# schematic.net
KiCad netlist of a schematic drawn in EAGLE
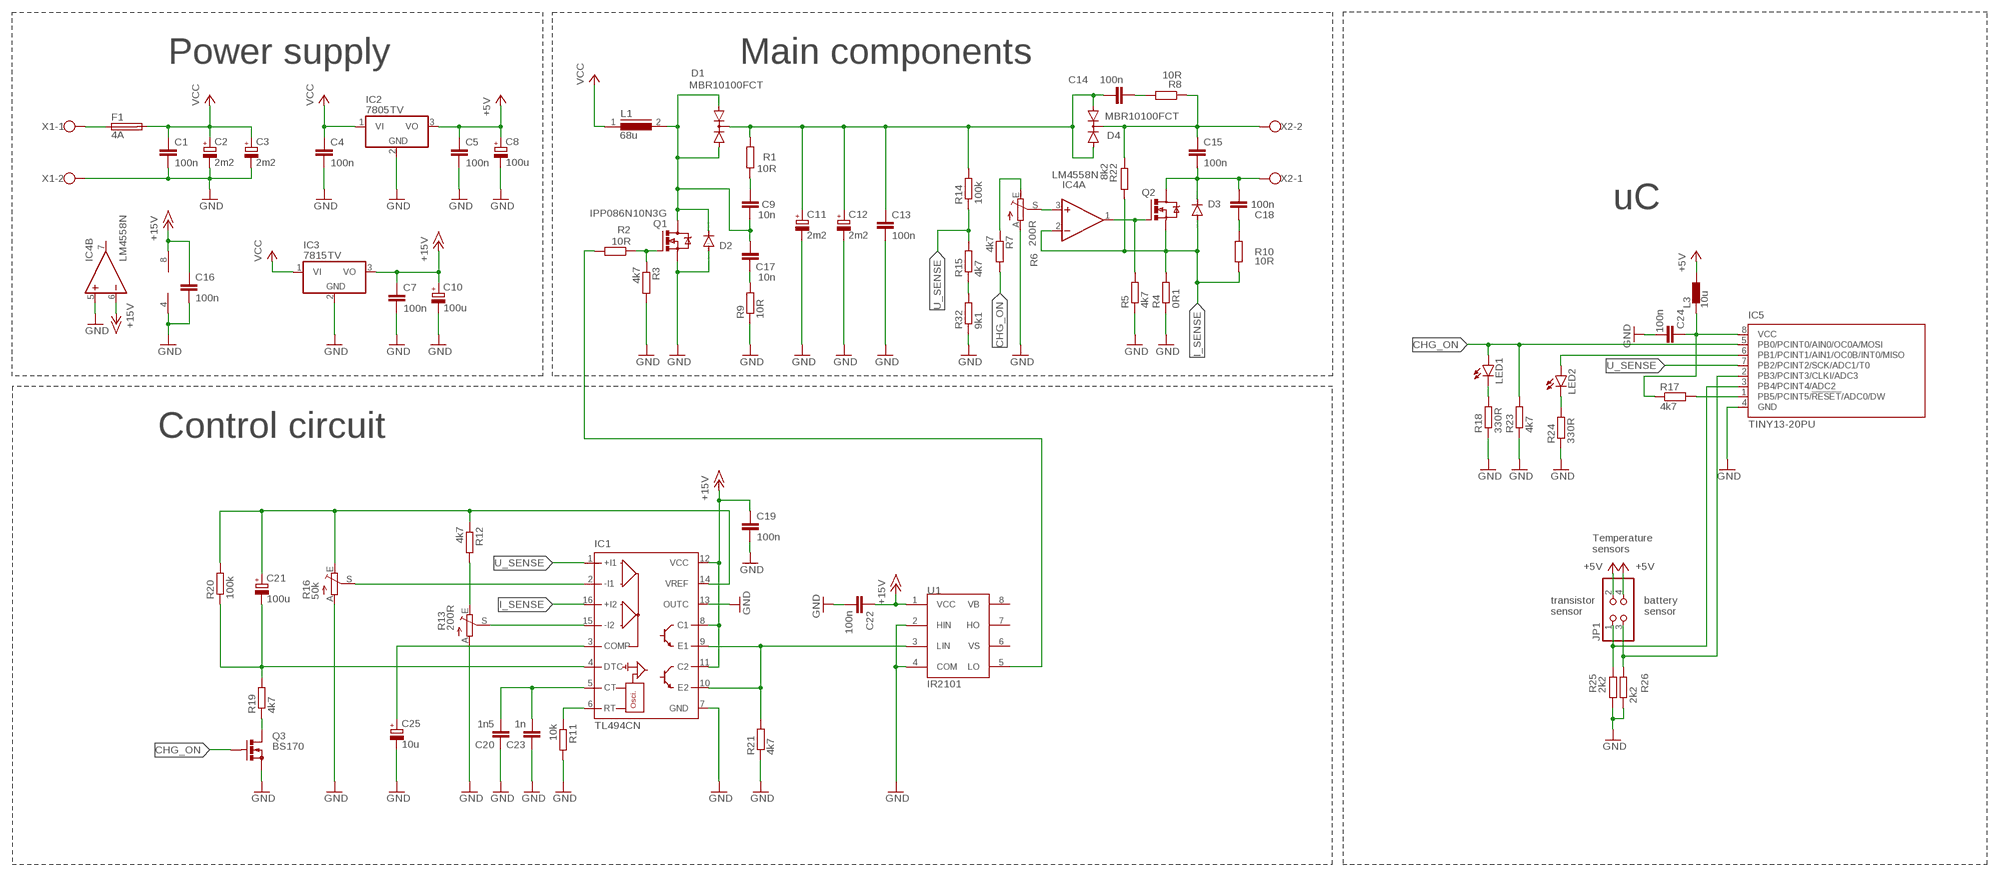
[diagram p0: schematic, sheet 1]

(export (version "E")
  (design (tool "Eeschema 10.0.6"))
  (components
    (comp (ref "C1")
      (value "100n")
      (footprint "eagle-import:C2.5-2")
      (libsource (lib "eagle-import") (part "C2.5/2"))
    )
    (comp (ref "C2")
      (value "2m2")
      (footprint "eagle-import:E7,5-16")
      (libsource (lib "eagle-import") (part "CPOL-EUE7.5-16"))
    )
    (comp (ref "C3")
      (value "2m2")
      (footprint "eagle-import:E7,5-16")
      (libsource (lib "eagle-import") (part "CPOL-EUE7.5-16"))
    )
    (comp (ref "C4")
      (value "100n")
      (footprint "eagle-import:C2.5-2")
      (libsource (lib "eagle-import") (part "C2.5/2"))
    )
    (comp (ref "C5")
      (value "100n")
      (footprint "eagle-import:C2.5-2")
      (libsource (lib "eagle-import") (part "C2.5/2"))
    )
    (comp (ref "C7")
      (value "100n")
      (footprint "eagle-import:C2.5-2")
      (libsource (lib "eagle-import") (part "C2.5/2"))
    )
    (comp (ref "C8")
      (value "100u")
      (footprint "eagle-import:E3,5-8")
      (libsource (lib "eagle-import") (part "CPOL-EUE3.5-8"))
    )
    (comp (ref "C9")
      (value "10n")
      (footprint "eagle-import:C2.5-2")
      (libsource (lib "eagle-import") (part "C2.5/2"))
    )
    (comp (ref "C10")
      (value "100u")
      (footprint "eagle-import:E3,5-8")
      (libsource (lib "eagle-import") (part "CPOL-EUE3.5-8"))
    )
    (comp (ref "C11")
      (value "2m2")
      (footprint "eagle-import:E7,5-18")
      (libsource (lib "eagle-import") (part "CPOL-EUE7.5-18"))
    )
    (comp (ref "C12")
      (value "2m2")
      (footprint "eagle-import:E7,5-18")
      (libsource (lib "eagle-import") (part "CPOL-EUE7.5-18"))
    )
    (comp (ref "C13")
      (value "100n")
      (footprint "eagle-import:C2.5-2")
      (libsource (lib "eagle-import") (part "C2.5/2"))
    )
    (comp (ref "C14")
      (value "100n")
      (footprint "eagle-import:C2.5-2")
      (libsource (lib "eagle-import") (part "C2.5/2"))
    )
    (comp (ref "C15")
      (value "100n")
      (footprint "eagle-import:C2.5-2")
      (libsource (lib "eagle-import") (part "C2.5/2"))
    )
    (comp (ref "C16")
      (value "100n")
      (footprint "eagle-import:C2.5-2")
      (libsource (lib "eagle-import") (part "C2.5/2"))
    )
    (comp (ref "C17")
      (value "10n")
      (footprint "eagle-import:C2.5-2")
      (libsource (lib "eagle-import") (part "C2.5/2"))
    )
    (comp (ref "C18")
      (value "100n")
      (footprint "eagle-import:C2.5-2")
      (libsource (lib "eagle-import") (part "C2.5/2"))
    )
    (comp (ref "C19")
      (value "100n")
      (footprint "eagle-import:C2.5-2")
      (libsource (lib "eagle-import") (part "C2.5/2"))
    )
    (comp (ref "C20")
      (value "1n5")
      (footprint "eagle-import:C2.5-2")
      (libsource (lib "eagle-import") (part "C2.5/2"))
    )
    (comp (ref "C21")
      (value "100u")
      (footprint "eagle-import:E3,5-8")
      (libsource (lib "eagle-import") (part "CPOL-EUE3.5-8"))
    )
    (comp (ref "C22")
      (value "100n")
      (footprint "eagle-import:C2.5-2")
      (libsource (lib "eagle-import") (part "C2.5/2"))
    )
    (comp (ref "C23")
      (value "1n")
      (footprint "eagle-import:C2.5-2")
      (libsource (lib "eagle-import") (part "C2.5/2"))
    )
    (comp (ref "C24")
      (value "100n")
      (footprint "eagle-import:C2.5-2")
      (libsource (lib "eagle-import") (part "C2.5/2"))
    )
    (comp (ref "C25")
      (value "10u")
      (footprint "eagle-import:E2,5-5")
      (libsource (lib "eagle-import") (part "CPOL-EUE2.5-5"))
    )
    (comp (ref "D1")
      (value "MBR10100FCT")
      (footprint "eagle-import:TO220ABS")
      (libsource (lib "eagle-import") (part "BYV32"))
    )
    (comp (ref "D2")
      (value "1N4933")
      (footprint "eagle-import:DO41-10")
      (libsource (lib "eagle-import") (part "1N4933"))
    )
    (comp (ref "D3")
      (value "1N4933")
      (footprint "eagle-import:DO41-10")
      (libsource (lib "eagle-import") (part "1N4933"))
    )
    (comp (ref "D4")
      (value "MBR10100FCT")
      (footprint "eagle-import:TO220ABS")
      (libsource (lib "eagle-import") (part "BYV32"))
    )
    (comp (ref "F1")
      (value "4A")
      (footprint "eagle-import:SH22")
      (libsource (lib "eagle-import") (part "SH22"))
    )
    (comp (ref "IC1")
      (value "TL494CN")
      (footprint "eagle-import:DIL16")
      (libsource (lib "eagle-import") (part "TL494NC"))
    )
    (comp (ref "IC2")
      (value "7805TV")
      (footprint "eagle-import:TO220V")
      (libsource (lib "eagle-import") (part "78TV05"))
    )
    (comp (ref "IC3")
      (value "7815TV")
      (footprint "eagle-import:TO220V")
      (libsource (lib "eagle-import") (part "78TV15"))
    )
    (comp (ref "IC4")
      (value "LM4558N")
      (footprint "eagle-import:DIL08")
      (libsource (lib "eagle-import") (part "4558NLM"))
    )
    (comp (ref "IC5")
      (value "TINY13-20PU")
      (footprint "eagle-import:DIL08")
      (fields (field (name "MPN") "ATTINY13-20PU"))
      (libsource (lib "eagle-import") (part "TINY13PU-20"))
    )
    (comp (ref "JP1")
      (value "PINHD-2X2")
      (footprint "eagle-import:2X02")
      (libsource (lib "eagle-import") (part "PINHD-2X2"))
    )
    (comp (ref "L1")
      (value "68u")
      (footprint "eagle-import:SFT1240")
      (libsource (lib "eagle-import") (part "SFT1240"))
    )
    (comp (ref "L3")
      (value "10u")
      (footprint "eagle-import:BL01RN1A")
      (libsource (lib "eagle-import") (part "BL01RN1A"))
    )
    (comp (ref "LED1")
      (value "LED5MM")
      (footprint "eagle-import:LED5MM")
      (libsource (lib "eagle-import") (part "LED5MM"))
    )
    (comp (ref "LED2")
      (value "LED5MM")
      (footprint "eagle-import:LED5MM")
      (libsource (lib "eagle-import") (part "LED5MM"))
    )
    (comp (ref "Q1")
      (value "IPP086N10N3G")
      (footprint "eagle-import:TO220BV")
      (libsource (lib "eagle-import") (part "IRF520"))
    )
    (comp (ref "Q2")
      (value "IRF520")
      (footprint "eagle-import:TO220BV")
      (libsource (lib "eagle-import") (part "IRF520"))
    )
    (comp (ref "Q3")
      (value "BS170")
      (footprint "eagle-import:SOT54E")
      (libsource (lib "eagle-import") (part "BS170"))
    )
    (comp (ref "R1")
      (value "10R")
      (footprint "eagle-import:0204_7")
      (libsource (lib "eagle-import") (part "R-EU_0204/7"))
    )
    (comp (ref "R2")
      (value "10R")
      (footprint "eagle-import:0204_7")
      (libsource (lib "eagle-import") (part "R-EU_0204/7"))
    )
    (comp (ref "R3")
      (value "4k7")
      (footprint "eagle-import:0204_7")
      (libsource (lib "eagle-import") (part "R-EU_0204/7"))
    )
    (comp (ref "R4")
      (value "0R1")
      (footprint "eagle-import:0204_5")
      (libsource (lib "eagle-import") (part "R-EU_0204/5"))
    )
    (comp (ref "R5")
      (value "4k7")
      (footprint "eagle-import:0204_7")
      (libsource (lib "eagle-import") (part "R-EU_0204/7"))
    )
    (comp (ref "R6")
      (value "200R")
      (footprint "eagle-import:B64Y")
      (libsource (lib "eagle-import") (part "TRIM_EU-B64Y"))
    )
    (comp (ref "R7")
      (value "4k7")
      (footprint "eagle-import:0204_7")
      (libsource (lib "eagle-import") (part "R-EU_0204/7"))
    )
    (comp (ref "R8")
      (value "10R")
      (footprint "eagle-import:0204_7")
      (libsource (lib "eagle-import") (part "R-EU_0204/7"))
    )
    (comp (ref "R9")
      (value "10R")
      (footprint "eagle-import:0204_7")
      (libsource (lib "eagle-import") (part "R-EU_0204/7"))
    )
    (comp (ref "R10")
      (value "10R")
      (footprint "eagle-import:0204_7")
      (libsource (lib "eagle-import") (part "R-EU_0204/7"))
    )
    (comp (ref "R11")
      (value "10k")
      (footprint "eagle-import:0204_7")
      (libsource (lib "eagle-import") (part "R-EU_0204/7"))
    )
    (comp (ref "R12")
      (value "4k7")
      (footprint "eagle-import:0204_7")
      (libsource (lib "eagle-import") (part "R-EU_0204/7"))
    )
    (comp (ref "R13")
      (value "200R")
      (footprint "eagle-import:B64Y")
      (libsource (lib "eagle-import") (part "TRIM_EU-B64Y"))
    )
    (comp (ref "R14")
      (value "100k")
      (footprint "eagle-import:0204_7")
      (libsource (lib "eagle-import") (part "R-EU_0204/7"))
    )
    (comp (ref "R15")
      (value "4k7")
      (footprint "eagle-import:0204_7")
      (libsource (lib "eagle-import") (part "R-EU_0204/7"))
    )
    (comp (ref "R16")
      (value "50k")
      (footprint "eagle-import:B64W")
      (libsource (lib "eagle-import") (part "TRIM_EU-B64W"))
    )
    (comp (ref "R17")
      (value "4k7")
      (footprint "eagle-import:0204_7")
      (libsource (lib "eagle-import") (part "R-EU_0204/7"))
    )
    (comp (ref "R18")
      (value "330R")
      (footprint "eagle-import:0204_7")
      (libsource (lib "eagle-import") (part "R-EU_0204/7"))
    )
    (comp (ref "R19")
      (value "4k7")
      (footprint "eagle-import:0204_7")
      (libsource (lib "eagle-import") (part "R-EU_0204/7"))
    )
    (comp (ref "R20")
      (value "100k")
      (footprint "eagle-import:0204_7")
      (libsource (lib "eagle-import") (part "R-EU_0204/7"))
    )
    (comp (ref "R21")
      (value "4k7")
      (footprint "eagle-import:0204_7")
      (libsource (lib "eagle-import") (part "R-EU_0204/7"))
    )
    (comp (ref "R22")
      (value "8k2")
      (footprint "eagle-import:0204_7")
      (libsource (lib "eagle-import") (part "R-EU_0204/7"))
    )
    (comp (ref "R23")
      (value "4k7")
      (footprint "eagle-import:0204_7")
      (libsource (lib "eagle-import") (part "R-EU_0204/7"))
    )
    (comp (ref "R24")
      (value "330R")
      (footprint "eagle-import:0204_7")
      (libsource (lib "eagle-import") (part "R-EU_0204/7"))
    )
    (comp (ref "R25")
      (value "2k2")
      (footprint "eagle-import:0204_7")
      (libsource (lib "eagle-import") (part "R-EU_0204/7"))
    )
    (comp (ref "R26")
      (value "2k2")
      (footprint "eagle-import:0204_7")
      (libsource (lib "eagle-import") (part "R-EU_0204/7"))
    )
    (comp (ref "R32")
      (value "9k1")
      (footprint "eagle-import:0204_7")
      (libsource (lib "eagle-import") (part "R-EU_0204/7"))
    )
    (comp (ref "U1")
      (value "IR2101")
      (footprint "eagle-import:DIL08")
      (libsource (lib "eagle-import") (part "IR2101"))
    )
    (comp (ref "X1")
      (value "W237-102")
      (footprint "eagle-import:W237-102")
      (fields (field (name "MPN") "237-102"))
      (libsource (lib "eagle-import") (part "W237-102"))
    )
    (comp (ref "X2")
      (value "W237-102")
      (footprint "eagle-import:W237-102")
      (fields (field (name "MPN") "237-102"))
      (libsource (lib "eagle-import") (part "W237-102"))
    )
  )
  (nets
    (net (code "1") (name "+5V") (class "Default")
      (node (ref "C5") (pin "1") (pinfunction "1_1") (pintype "passive"))
      (node (ref "C8") (pin "+") (pinfunction "+_+") (pintype "passive"))
      (node (ref "IC2") (pin "3") (pinfunction "VO_3") (pintype "passive"))
      (node (ref "JP1") (pin "2") (pinfunction "2_2") (pintype "passive"))
      (node (ref "JP1") (pin "4") (pinfunction "4_4") (pintype "passive"))
      (node (ref "L3") (pin "2") (pinfunction "2_2") (pintype "passive"))
    )
    (net (code "2") (name "+15V") (class "Default")
      (node (ref "C10") (pin "+") (pinfunction "+_+") (pintype "passive"))
      (node (ref "C16") (pin "1") (pinfunction "1_1") (pintype "passive"))
      (node (ref "C19") (pin "1") (pinfunction "1_1") (pintype "passive"))
      (node (ref "C22") (pin "1") (pinfunction "1_1") (pintype "passive"))
      (node (ref "C7") (pin "1") (pinfunction "1_1") (pintype "passive"))
      (node (ref "IC1") (pin "11") (pinfunction "C2_11") (pintype "passive"))
      (node (ref "IC1") (pin "12") (pinfunction "VCC_12") (pintype "power_in"))
      (node (ref "IC1") (pin "8") (pinfunction "C1_8") (pintype "passive"))
      (node (ref "IC3") (pin "3") (pinfunction "VO_3") (pintype "passive"))
      (node (ref "IC4") (pin "6") (pinfunction "-IN_6") (pintype "input"))
      (node (ref "IC4") (pin "8") (pinfunction "V+_8") (pintype "power_in"))
      (node (ref "U1") (pin "1") (pinfunction "VCC_1") (pintype "power_in"))
    )
    (net (code "3") (name "/VB") (class "Default")
      (node (ref "U1") (pin "8") (pinfunction "VB_8") (pintype "power_in"))
    )
    (net (code "4") (name "CHG_ON") (class "Default")
      (node (ref "IC5") (pin "5") (pinfunction "PB0/PCINT0/AIN0/OC0A/MOSI_5") (pintype "bidirectional"))
      (node (ref "LED1") (pin "A") (pinfunction "A_A") (pintype "passive"))
      (node (ref "Q3") (pin "G") (pinfunction "G_G") (pintype "passive"))
      (node (ref "R23") (pin "2") (pinfunction "2_2") (pintype "passive"))
      (node (ref "R7") (pin "2") (pinfunction "2_2") (pintype "passive"))
    )
    (net (code "5") (name "GND") (class "Default")
      (node (ref "C1") (pin "2") (pinfunction "2_2") (pintype "passive"))
      (node (ref "C10") (pin "-") (pinfunction "-_-") (pintype "passive"))
      (node (ref "C11") (pin "-") (pinfunction "-_-") (pintype "passive"))
      (node (ref "C12") (pin "-") (pinfunction "-_-") (pintype "passive"))
      (node (ref "C13") (pin "2") (pinfunction "2_2") (pintype "passive"))
      (node (ref "C16") (pin "2") (pinfunction "2_2") (pintype "passive"))
      (node (ref "C19") (pin "2") (pinfunction "2_2") (pintype "passive"))
      (node (ref "C2") (pin "-") (pinfunction "-_-") (pintype "passive"))
      (node (ref "C20") (pin "1") (pinfunction "1_1") (pintype "passive"))
      (node (ref "C22") (pin "2") (pinfunction "2_2") (pintype "passive"))
      (node (ref "C23") (pin "1") (pinfunction "1_1") (pintype "passive"))
      (node (ref "C24") (pin "2") (pinfunction "2_2") (pintype "passive"))
      (node (ref "C25") (pin "-") (pinfunction "-_-") (pintype "passive"))
      (node (ref "C3") (pin "-") (pinfunction "-_-") (pintype "passive"))
      (node (ref "C4") (pin "2") (pinfunction "2_2") (pintype "passive"))
      (node (ref "C5") (pin "2") (pinfunction "2_2") (pintype "passive"))
      (node (ref "C7") (pin "2") (pinfunction "2_2") (pintype "passive"))
      (node (ref "C8") (pin "-") (pinfunction "-_-") (pintype "passive"))
      (node (ref "D2") (pin "A") (pinfunction "A_A") (pintype "passive"))
      (node (ref "IC1") (pin "13") (pinfunction "OUTC_13") (pintype "output"))
      (node (ref "IC1") (pin "7") (pinfunction "GND_7") (pintype "power_in"))
      (node (ref "IC2") (pin "2") (pinfunction "GND_2") (pintype "passive"))
      (node (ref "IC3") (pin "2") (pinfunction "GND_2") (pintype "passive"))
      (node (ref "IC4") (pin "4") (pinfunction "V-_4") (pintype "power_in"))
      (node (ref "IC4") (pin "5") (pinfunction "+IN_5") (pintype "input"))
      (node (ref "IC5") (pin "4") (pinfunction "GND_4") (pintype "power_in"))
      (node (ref "Q1") (pin "S") (pinfunction "S_S") (pintype "passive"))
      (node (ref "Q3") (pin "S") (pinfunction "S_S") (pintype "passive"))
      (node (ref "R11") (pin "2") (pinfunction "2_2") (pintype "passive"))
      (node (ref "R13") (pin "A") (pinfunction "A_A") (pintype "passive"))
      (node (ref "R16") (pin "A") (pinfunction "A_A") (pintype "passive"))
      (node (ref "R18") (pin "1") (pinfunction "1_1") (pintype "passive"))
      (node (ref "R21") (pin "1") (pinfunction "1_1") (pintype "passive"))
      (node (ref "R23") (pin "1") (pinfunction "1_1") (pintype "passive"))
      (node (ref "R24") (pin "1") (pinfunction "1_1") (pintype "passive"))
      (node (ref "R25") (pin "1") (pinfunction "1_1") (pintype "passive"))
      (node (ref "R26") (pin "1") (pinfunction "1_1") (pintype "passive"))
      (node (ref "R3") (pin "2") (pinfunction "2_2") (pintype "passive"))
      (node (ref "R32") (pin "1") (pinfunction "1_1") (pintype "passive"))
      (node (ref "R4") (pin "1") (pinfunction "1_1") (pintype "passive"))
      (node (ref "R5") (pin "1") (pinfunction "1_1") (pintype "passive"))
      (node (ref "R6") (pin "A") (pinfunction "A_A") (pintype "passive"))
      (node (ref "R9") (pin "1") (pinfunction "1_1") (pintype "passive"))
      (node (ref "U1") (pin "2") (pinfunction "HIN_2") (pintype "input"))
      (node (ref "U1") (pin "4") (pinfunction "COM_4") (pintype "power_in"))
      (node (ref "X1") (pin "2") (pinfunction "KL_2") (pintype "passive"))
    )
    (net (code "6") (name "I_SENSE") (class "Default")
      (node (ref "D3") (pin "A") (pinfunction "A_A") (pintype "passive"))
      (node (ref "IC1") (pin "16") (pinfunction "+I2_16") (pintype "input"))
      (node (ref "IC4") (pin "2") (pinfunction "-IN_2") (pintype "input"))
      (node (ref "Q2") (pin "S") (pinfunction "S_S") (pintype "passive"))
      (node (ref "R10") (pin "2") (pinfunction "2_2") (pintype "passive"))
      (node (ref "R22") (pin "2") (pinfunction "2_2") (pintype "passive"))
      (node (ref "R4") (pin "2") (pinfunction "2_2") (pintype "passive"))
    )
    (net (code "7") (name "Net-(C9-Pad1)") (class "Default")
      (node (ref "C9") (pin "1") (pinfunction "1_1") (pintype "passive"))
      (node (ref "R1") (pin "1") (pinfunction "1_1") (pintype "passive"))
    )
    (net (code "8") (name "Net-(C11-Pad+)") (class "Default")
      (node (ref "C11") (pin "+") (pinfunction "+_+") (pintype "passive"))
      (node (ref "C12") (pin "+") (pinfunction "+_+") (pintype "passive"))
      (node (ref "C13") (pin "1") (pinfunction "1_1") (pintype "passive"))
      (node (ref "C14") (pin "2") (pinfunction "2_2") (pintype "passive"))
      (node (ref "D1") (pin "C") (pinfunction "C_C") (pintype "passive"))
      (node (ref "D4") (pin "A1") (pinfunction "A1_A1") (pintype "passive"))
      (node (ref "D4") (pin "A2") (pinfunction "A2_A2") (pintype "passive"))
      (node (ref "R1") (pin "2") (pinfunction "2_2") (pintype "passive"))
      (node (ref "R14") (pin "2") (pinfunction "2_2") (pintype "passive"))
    )
    (net (code "9") (name "Net-(C14-Pad1)") (class "Default")
      (node (ref "C14") (pin "1") (pinfunction "1_1") (pintype "passive"))
      (node (ref "R8") (pin "2") (pinfunction "2_2") (pintype "passive"))
    )
    (net (code "10") (name "Net-(C17-Pad1)") (class "Default")
      (node (ref "C17") (pin "1") (pinfunction "1_1") (pintype "passive"))
      (node (ref "C9") (pin "2") (pinfunction "2_2") (pintype "passive"))
      (node (ref "D1") (pin "A1") (pinfunction "A1_A1") (pintype "passive"))
      (node (ref "D1") (pin "A2") (pinfunction "A2_A2") (pintype "passive"))
      (node (ref "D2") (pin "C") (pinfunction "C_C") (pintype "passive"))
      (node (ref "L1") (pin "2") (pinfunction "2_2") (pintype "passive"))
      (node (ref "Q1") (pin "D") (pinfunction "D_D") (pintype "passive"))
    )
    (net (code "11") (name "Net-(C17-Pad2)") (class "Default")
      (node (ref "C17") (pin "2") (pinfunction "2_2") (pintype "passive"))
      (node (ref "R9") (pin "2") (pinfunction "2_2") (pintype "passive"))
    )
    (net (code "12") (name "Net-(C18-Pad2)") (class "Default")
      (node (ref "C18") (pin "2") (pinfunction "2_2") (pintype "passive"))
      (node (ref "R10") (pin "1") (pinfunction "1_1") (pintype "passive"))
    )
    (net (code "13") (name "Net-(IC1--I1)") (class "Default")
      (node (ref "IC1") (pin "2") (pinfunction "-I1_2") (pintype "input"))
      (node (ref "R16") (pin "S") (pinfunction "S_S") (pintype "passive"))
    )
    (net (code "14") (name "Net-(IC1--I2)") (class "Default")
      (node (ref "IC1") (pin "15") (pinfunction "-I2_15") (pintype "input"))
      (node (ref "R13") (pin "S") (pinfunction "S_S") (pintype "passive"))
    )
    (net (code "15") (name "Net-(IC1-COMP)") (class "Default")
      (node (ref "C25") (pin "+") (pinfunction "+_+") (pintype "passive"))
      (node (ref "IC1") (pin "3") (pinfunction "COMP_3") (pintype "passive"))
    )
    (net (code "16") (name "Net-(IC1-CT)") (class "Default")
      (node (ref "C20") (pin "2") (pinfunction "2_2") (pintype "passive"))
      (node (ref "C23") (pin "2") (pinfunction "2_2") (pintype "passive"))
      (node (ref "IC1") (pin "5") (pinfunction "CT_5") (pintype "input"))
    )
    (net (code "17") (name "Net-(IC1-DTC)") (class "Default")
      (node (ref "C21") (pin "-") (pinfunction "-_-") (pintype "passive"))
      (node (ref "IC1") (pin "4") (pinfunction "DTC_4") (pintype "input"))
      (node (ref "R19") (pin "2") (pinfunction "2_2") (pintype "passive"))
      (node (ref "R20") (pin "1") (pinfunction "1_1") (pintype "passive"))
    )
    (net (code "18") (name "Net-(IC1-E1)") (class "Default")
      (node (ref "IC1") (pin "10") (pinfunction "E2_10") (pintype "passive"))
      (node (ref "IC1") (pin "9") (pinfunction "E1_9") (pintype "passive"))
      (node (ref "R21") (pin "2") (pinfunction "2_2") (pintype "passive"))
      (node (ref "U1") (pin "3") (pinfunction "LIN_3") (pintype "input"))
    )
    (net (code "19") (name "Net-(IC1-RT)") (class "Default")
      (node (ref "IC1") (pin "6") (pinfunction "RT_6") (pintype "input"))
      (node (ref "R11") (pin "1") (pinfunction "1_1") (pintype "passive"))
    )
    (net (code "20") (name "Net-(IC1-VREF)") (class "Default")
      (node (ref "C21") (pin "+") (pinfunction "+_+") (pintype "passive"))
      (node (ref "IC1") (pin "14") (pinfunction "VREF_14") (pintype "input"))
      (node (ref "R12") (pin "1") (pinfunction "1_1") (pintype "passive"))
      (node (ref "R16") (pin "E") (pinfunction "E_E") (pintype "passive"))
      (node (ref "R20") (pin "2") (pinfunction "2_2") (pintype "passive"))
    )
    (net (code "21") (name "Net-(IC4A-+IN)") (class "Default")
      (node (ref "IC4") (pin "3") (pinfunction "+IN_3") (pintype "input"))
      (node (ref "R6") (pin "S") (pinfunction "S_S") (pintype "passive"))
    )
    (net (code "22") (name "Net-(IC4A-OUT)") (class "Default")
      (node (ref "IC4") (pin "1") (pinfunction "OUT_1") (pintype "output"))
      (node (ref "Q2") (pin "G") (pinfunction "G_G") (pintype "passive"))
      (node (ref "R5") (pin "2") (pinfunction "2_2") (pintype "passive"))
    )
    (net (code "23") (name "Net-(IC5-PB1{slash}PCINT1{slash}AIN1{slash}OC0B{slash}INT0{slash}MISO)") (class "Default")
      (node (ref "IC5") (pin "6") (pinfunction "PB1/PCINT1/AIN1/OC0B/INT0/MISO_6") (pintype "bidirectional"))
      (node (ref "LED2") (pin "A") (pinfunction "A_A") (pintype "passive"))
    )
    (net (code "24") (name "Net-(IC5-PB3{slash}PCINT3{slash}CLKI{slash}ADC3)") (class "Default")
      (node (ref "IC5") (pin "2") (pinfunction "PB3/PCINT3/CLKI/ADC3_2") (pintype "bidirectional"))
      (node (ref "JP1") (pin "3") (pinfunction "3_3") (pintype "passive"))
      (node (ref "R26") (pin "2") (pinfunction "2_2") (pintype "passive"))
    )
    (net (code "25") (name "Net-(IC5-PB4{slash}PCINT4{slash}ADC2)") (class "Default")
      (node (ref "IC5") (pin "3") (pinfunction "PB4/PCINT4/ADC2_3") (pintype "bidirectional"))
      (node (ref "JP1") (pin "1") (pinfunction "1_1") (pintype "passive"))
      (node (ref "R25") (pin "2") (pinfunction "2_2") (pintype "passive"))
    )
    (net (code "26") (name "Net-(IC5-PB5{slash}PCINT5{slash}~{RESET}{slash}ADC0{slash}DW)") (class "Default")
      (node (ref "IC5") (pin "1") (pinfunction "PB5/PCINT5/~{RESET}/ADC0/DW_1") (pintype "bidirectional"))
      (node (ref "R17") (pin "2") (pinfunction "2_2") (pintype "passive"))
    )
    (net (code "27") (name "Net-(IC5-VCC)") (class "Default")
      (node (ref "C24") (pin "1") (pinfunction "1_1") (pintype "passive"))
      (node (ref "IC5") (pin "8") (pinfunction "VCC_8") (pintype "power_in"))
      (node (ref "L3") (pin "1") (pinfunction "1_1") (pintype "passive"))
      (node (ref "R17") (pin "1") (pinfunction "1_1") (pintype "passive"))
    )
    (net (code "28") (name "Net-(LED1-C)") (class "Default")
      (node (ref "LED1") (pin "K") (pinfunction "C_K") (pintype "passive"))
      (node (ref "R18") (pin "2") (pinfunction "2_2") (pintype "passive"))
    )
    (net (code "29") (name "Net-(LED2-C)") (class "Default")
      (node (ref "LED2") (pin "K") (pinfunction "C_K") (pintype "passive"))
      (node (ref "R24") (pin "2") (pinfunction "2_2") (pintype "passive"))
    )
    (net (code "30") (name "Net-(Q1-PadG)") (class "Default")
      (node (ref "Q1") (pin "G") (pinfunction "G_G") (pintype "passive"))
      (node (ref "R2") (pin "1") (pinfunction "1_1") (pintype "passive"))
      (node (ref "R3") (pin "1") (pinfunction "1_1") (pintype "passive"))
    )
    (net (code "31") (name "Net-(Q3-PadD)") (class "Default")
      (node (ref "Q3") (pin "D") (pinfunction "D_D") (pintype "passive"))
      (node (ref "R19") (pin "1") (pinfunction "1_1") (pintype "passive"))
    )
    (net (code "32") (name "Net-(R6-PadE)") (class "Default")
      (node (ref "R6") (pin "E") (pinfunction "E_E") (pintype "passive"))
      (node (ref "R7") (pin "1") (pinfunction "1_1") (pintype "passive"))
    )
    (net (code "33") (name "Net-(R12-Pad2)") (class "Default")
      (node (ref "R12") (pin "2") (pinfunction "2_2") (pintype "passive"))
      (node (ref "R13") (pin "E") (pinfunction "E_E") (pintype "passive"))
    )
    (net (code "34") (name "Net-(R15-Pad1)") (class "Default")
      (node (ref "R15") (pin "1") (pinfunction "1_1") (pintype "passive"))
      (node (ref "R32") (pin "2") (pinfunction "2_2") (pintype "passive"))
    )
    (net (code "35") (name "Net-(U1-LO)") (class "Default")
      (node (ref "R2") (pin "2") (pinfunction "2_2") (pintype "passive"))
      (node (ref "U1") (pin "5") (pinfunction "LO_5") (pintype "output"))
    )
    (net (code "36") (name "Net-(X1A-KL)") (class "Default")
      (node (ref "F1") (pin "1") (pinfunction "1_1") (pintype "passive"))
      (node (ref "X1") (pin "1") (pinfunction "KL_1") (pintype "passive"))
    )
    (net (code "37") (name "Net-(X2A-KL)") (class "Default")
      (node (ref "C15") (pin "2") (pinfunction "2_2") (pintype "passive"))
      (node (ref "C18") (pin "1") (pinfunction "1_1") (pintype "passive"))
      (node (ref "D3") (pin "C") (pinfunction "C_C") (pintype "passive"))
      (node (ref "Q2") (pin "D") (pinfunction "D_D") (pintype "passive"))
      (node (ref "X2") (pin "1") (pinfunction "KL_1") (pintype "passive"))
    )
    (net (code "38") (name "Net-(X2B-KL)") (class "Default")
      (node (ref "C15") (pin "1") (pinfunction "1_1") (pintype "passive"))
      (node (ref "D4") (pin "C") (pinfunction "C_C") (pintype "passive"))
      (node (ref "R22") (pin "1") (pinfunction "1_1") (pintype "passive"))
      (node (ref "R8") (pin "1") (pinfunction "1_1") (pintype "passive"))
      (node (ref "X2") (pin "2") (pinfunction "KL_2") (pintype "passive"))
    )
    (net (code "39") (name "U_SENSE") (class "Default")
      (node (ref "IC1") (pin "1") (pinfunction "+I1_1") (pintype "input"))
      (node (ref "IC5") (pin "7") (pinfunction "PB2/PCINT2/SCK/ADC1/T0_7") (pintype "bidirectional"))
      (node (ref "R14") (pin "1") (pinfunction "1_1") (pintype "passive"))
      (node (ref "R15") (pin "2") (pinfunction "2_2") (pintype "passive"))
    )
    (net (code "40") (name "VCC") (class "Default")
      (node (ref "C1") (pin "1") (pinfunction "1_1") (pintype "passive"))
      (node (ref "C2") (pin "+") (pinfunction "+_+") (pintype "passive"))
      (node (ref "C3") (pin "+") (pinfunction "+_+") (pintype "passive"))
      (node (ref "C4") (pin "1") (pinfunction "1_1") (pintype "passive"))
      (node (ref "F1") (pin "2") (pinfunction "2_2") (pintype "passive"))
      (node (ref "IC2") (pin "1") (pinfunction "VI_1") (pintype "input"))
      (node (ref "IC3") (pin "1") (pinfunction "VI_1") (pintype "input"))
      (node (ref "L1") (pin "1") (pinfunction "1_1") (pintype "passive"))
    )
    (net (code "41") (name "unconnected-(IC4B-OUT-Pad7)") (class "Default")
      (node (ref "IC4") (pin "7") (pinfunction "OUT_7") (pintype "output"))
    )
    (net (code "42") (name "unconnected-(U1-HO-Pad7)") (class "Default")
      (node (ref "U1") (pin "7") (pinfunction "HO_7") (pintype "output"))
    )
    (net (code "43") (name "unconnected-(U1-VS-Pad6)") (class "Default")
      (node (ref "U1") (pin "6") (pinfunction "VS_6") (pintype "output"))
    )
  )
)
